# Sh2_MCU.net
KiCad netlist of a schematic drawn in Altium Designer
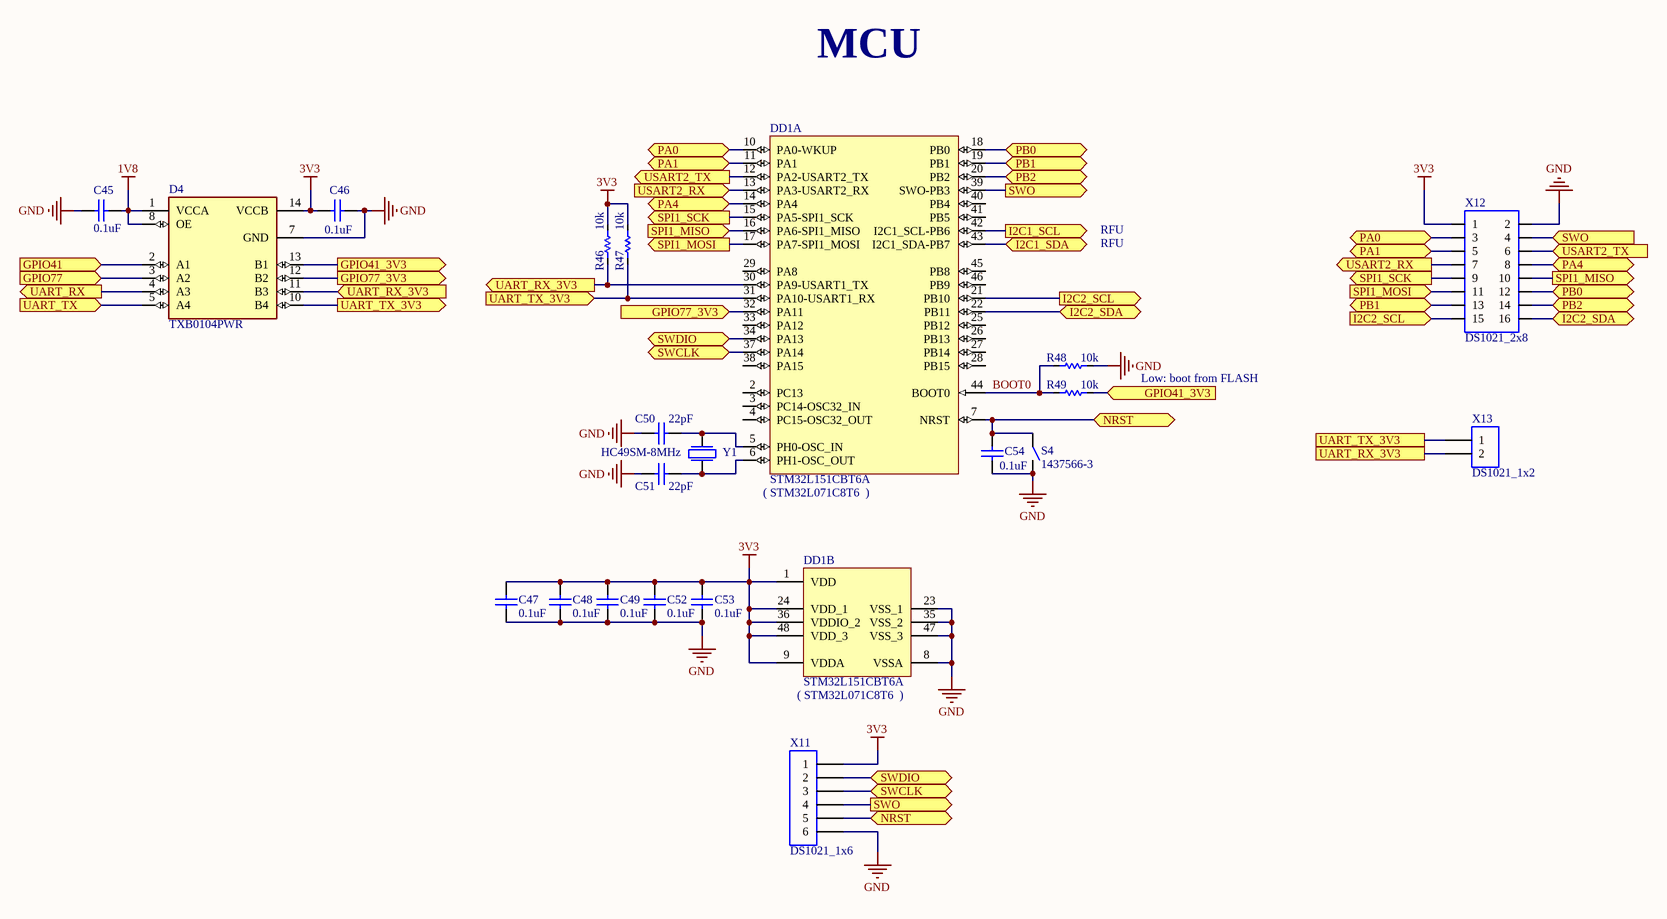
[diagram p0: Sh2_MCU.SchDoc]

(export (version "E")
  (design (tool "Eeschema 10.0.6"))
  (components
    (comp (ref "C45")
      (value "0.1uF")
      (footprint "C_SMD0603")
      (description "0603 SMD Capacitor")
      (libsource (lib "MyCompLib") (part "C_SMD"))
    )
    (comp (ref "C46")
      (value "0.1uF")
      (footprint "C_SMD0603")
      (description "0603 SMD Capacitor")
      (libsource (lib "MyCompLib") (part "C_SMD"))
    )
    (comp (ref "C47")
      (value "0.1uF")
      (footprint "C_SMD0603")
      (description "0603 SMD Capacitor")
      (libsource (lib "MyCompLib") (part "C_SMD"))
    )
    (comp (ref "C48")
      (value "0.1uF")
      (footprint "C_SMD0603")
      (description "0603 SMD Capacitor")
      (libsource (lib "MyCompLib") (part "C_SMD"))
    )
    (comp (ref "C49")
      (value "0.1uF")
      (footprint "C_SMD0603")
      (description "0603 SMD Capacitor")
      (libsource (lib "MyCompLib") (part "C_SMD"))
    )
    (comp (ref "C50")
      (value "22pF")
      (footprint "C_SMD0603")
      (description "0603 SMD Capacitor")
      (libsource (lib "MyCompLib") (part "C_SMD"))
    )
    (comp (ref "C51")
      (value "22pF")
      (footprint "C_SMD0603")
      (description "0603 SMD Capacitor")
      (libsource (lib "MyCompLib") (part "C_SMD"))
    )
    (comp (ref "C52")
      (value "0.1uF")
      (footprint "C_SMD0603")
      (description "0603 SMD Capacitor")
      (libsource (lib "MyCompLib") (part "C_SMD"))
    )
    (comp (ref "C53")
      (value "0.1uF")
      (footprint "C_SMD0603")
      (description "0603 SMD Capacitor")
      (libsource (lib "MyCompLib") (part "C_SMD"))
    )
    (comp (ref "C54")
      (value "0.1uF")
      (footprint "C_SMD0603")
      (description "0603 SMD Capacitor")
      (libsource (lib "MyCompLib") (part "C_SMD"))
    )
    (comp (ref "D4")
      (value "TXB0104PWR")
      (footprint "SOP65P640X120-14N")
      (fields (field (name "MF") "Texas Instruments"))
      (libsource (lib "MyCompLib") (part "TXB0104PWR"))
    )
    (comp (ref "DD1")
      (value "STM32L151CBT6A")
      (footprint "LQFP48_N")
      (fields (field (name "PARTNUMBER") "STM32F103C8T6"))
      (libsource (lib "MyCompLib") (part "STM32L151CBT6A"))
    )
    (comp (ref "R46")
      (value "10k")
      (footprint "R_SMD0603")
      (description "0603 SMD Resistor")
      (libsource (lib "MyCompLib") (part "R_SMD"))
    )
    (comp (ref "R47")
      (value "10k")
      (footprint "R_SMD0603")
      (description "0603 SMD Resistor")
      (libsource (lib "MyCompLib") (part "R_SMD"))
    )
    (comp (ref "R48")
      (value "10k")
      (footprint "R_SMD0603")
      (description "0603 SMD Resistor")
      (libsource (lib "MyCompLib") (part "R_SMD"))
    )
    (comp (ref "R49")
      (value "10k")
      (footprint "R_SMD0603")
      (description "0603 SMD Resistor")
      (libsource (lib "MyCompLib") (part "R_SMD"))
    )
    (comp (ref "S4")
      (value "1437566-3")
      (footprint "1437566-3")
      (description "SMD button")
      (libsource (lib "MyCompLib") (part "1437566-3"))
    )
    (comp (ref "X11")
      (value "DS1021_1x6")
      (footprint "PLD1X6")
      (description "Вилка штыревая 2.54мм 1x6 прямая тип1\r\n(PLS-6)")
      (libsource (lib "MyCompLib") (part "DS1021_1x6"))
    )
    (comp (ref "X12")
      (value "DS1021_2x8")
      (footprint "PLD2X8")
      (description "Вилка штыревая 2.54мм 2х8 прямая PLD-16")
      (libsource (lib "MyCompLib") (part "DS1021_2x8"))
    )
    (comp (ref "X13")
      (value "DS1021_1x2")
      (footprint "PLD2")
      (description "Вилка штыревая 2.54мм 1x2 прямая PLS-2")
      (libsource (lib "MyCompLib") (part "DS1021_1x2"))
    )
    (comp (ref "Y1")
      (value "HC49SM-8MHz")
      (footprint "HC49SM")
      (description "8 MHz resonator")
      (libsource (lib "MyCompLib") (part "HC49SM"))
    )
  )
  (nets
    (net (code "1") (name "/BOOT0") (class "Default")
      (node (ref "DD1") (pin "44") (pinfunction "BOOT0_44") (pintype "input"))
      (node (ref "R48") (pin "1") (pinfunction "CCW_1") (pintype "passive"))
      (node (ref "R49") (pin "1") (pinfunction "CCW_1") (pintype "passive"))
    )
    (net (code "2") (name "/GPIO41") (class "Default")
      (node (ref "D4") (pin "2") (pinfunction "A1_2") (pintype "bidirectional"))
    )
    (net (code "3") (name "/GPIO41_3V3") (class "Default")
      (node (ref "D4") (pin "13") (pinfunction "B1_13") (pintype "bidirectional"))
      (node (ref "R49") (pin "2") (pinfunction "CW_2") (pintype "passive"))
    )
    (net (code "4") (name "/GPIO77") (class "Default")
      (node (ref "D4") (pin "3") (pinfunction "A2_3") (pintype "bidirectional"))
    )
    (net (code "5") (name "/GPIO77_3V3") (class "Default")
      (node (ref "D4") (pin "12") (pinfunction "B2_12") (pintype "bidirectional"))
      (node (ref "DD1") (pin "32") (pinfunction "PA11_32") (pintype "bidirectional"))
    )
    (net (code "6") (name "/I2C1_SCL") (class "Default")
      (node (ref "DD1") (pin "42") (pinfunction "I2C1_SCL-PB6_42") (pintype "bidirectional"))
    )
    (net (code "7") (name "/I2C1_SDA") (class "Default")
      (node (ref "DD1") (pin "43") (pinfunction "I2C1_SDA-PB7_43") (pintype "bidirectional"))
    )
    (net (code "8") (name "/I2C2_SCL") (class "Default")
      (node (ref "DD1") (pin "21") (pinfunction "PB10_21") (pintype "bidirectional"))
      (node (ref "X12") (pin "15") (pinfunction "15_15") (pintype "passive"))
    )
    (net (code "9") (name "/I2C2_SDA") (class "Default")
      (node (ref "DD1") (pin "22") (pinfunction "PB11_22") (pintype "bidirectional"))
      (node (ref "X12") (pin "16") (pinfunction "16_16") (pintype "passive"))
    )
    (net (code "10") (name "/NRST") (class "Default")
      (node (ref "C54") (pin "1") (pinfunction "1_1") (pintype "passive"))
      (node (ref "DD1") (pin "7") (pinfunction "NRST_7") (pintype "bidirectional"))
      (node (ref "S4") (pin "1") (pinfunction "1_1") (pintype "passive"))
      (node (ref "X11") (pin "5") (pinfunction "5_5") (pintype "passive"))
    )
    (net (code "11") (name "/PA0") (class "Default")
      (node (ref "DD1") (pin "10") (pinfunction "PA0-WKUP_10") (pintype "bidirectional"))
      (node (ref "X12") (pin "3") (pinfunction "3_3") (pintype "passive"))
    )
    (net (code "12") (name "/PA1") (class "Default")
      (node (ref "DD1") (pin "11") (pinfunction "PA1_11") (pintype "bidirectional"))
      (node (ref "X12") (pin "5") (pinfunction "5_5") (pintype "passive"))
    )
    (net (code "13") (name "/PA4") (class "Default")
      (node (ref "DD1") (pin "14") (pinfunction "PA4_14") (pintype "bidirectional"))
      (node (ref "X12") (pin "8") (pinfunction "8_8") (pintype "passive"))
    )
    (net (code "14") (name "/PB0") (class "Default")
      (node (ref "DD1") (pin "18") (pinfunction "PB0_18") (pintype "bidirectional"))
      (node (ref "X12") (pin "12") (pinfunction "12_12") (pintype "passive"))
    )
    (net (code "15") (name "/PB1") (class "Default")
      (node (ref "DD1") (pin "19") (pinfunction "PB1_19") (pintype "bidirectional"))
      (node (ref "X12") (pin "13") (pinfunction "13_13") (pintype "passive"))
    )
    (net (code "16") (name "/PB2") (class "Default")
      (node (ref "DD1") (pin "20") (pinfunction "PB2_20") (pintype "bidirectional"))
      (node (ref "X12") (pin "14") (pinfunction "14_14") (pintype "passive"))
    )
    (net (code "17") (name "/SPI1_MISO") (class "Default")
      (node (ref "DD1") (pin "16") (pinfunction "PA6-SPI1_MISO_16") (pintype "bidirectional"))
      (node (ref "X12") (pin "10") (pinfunction "10_10") (pintype "passive"))
    )
    (net (code "18") (name "/SPI1_MOSI") (class "Default")
      (node (ref "DD1") (pin "17") (pinfunction "PA7-SPI1_MOSI_17") (pintype "bidirectional"))
      (node (ref "X12") (pin "11") (pinfunction "11_11") (pintype "passive"))
    )
    (net (code "19") (name "/SPI1_SCK") (class "Default")
      (node (ref "DD1") (pin "15") (pinfunction "PA5-SPI1_SCK_15") (pintype "bidirectional"))
      (node (ref "X12") (pin "9") (pinfunction "9_9") (pintype "passive"))
    )
    (net (code "20") (name "/SWCLK") (class "Default")
      (node (ref "DD1") (pin "37") (pinfunction "PA14_37") (pintype "bidirectional"))
      (node (ref "X11") (pin "3") (pinfunction "3_3") (pintype "passive"))
    )
    (net (code "21") (name "/SWDIO") (class "Default")
      (node (ref "DD1") (pin "34") (pinfunction "PA13_34") (pintype "bidirectional"))
      (node (ref "X11") (pin "2") (pinfunction "2_2") (pintype "passive"))
    )
    (net (code "22") (name "/SWO") (class "Default")
      (node (ref "DD1") (pin "39") (pinfunction "SWO-PB3_39") (pintype "bidirectional"))
      (node (ref "X11") (pin "4") (pinfunction "4_4") (pintype "passive"))
      (node (ref "X12") (pin "4") (pinfunction "4_4") (pintype "passive"))
    )
    (net (code "23") (name "/UART_RX") (class "Default")
      (node (ref "D4") (pin "4") (pinfunction "A3_4") (pintype "bidirectional"))
    )
    (net (code "24") (name "/UART_RX_3V3") (class "Default")
      (node (ref "D4") (pin "11") (pinfunction "B3_11") (pintype "bidirectional"))
      (node (ref "DD1") (pin "30") (pinfunction "PA9-USART1_TX_30") (pintype "bidirectional"))
      (node (ref "R46") (pin "2") (pinfunction "CW_2") (pintype "passive"))
      (node (ref "X13") (pin "2") (pinfunction "2_2") (pintype "passive"))
    )
    (net (code "25") (name "/UART_TX") (class "Default")
      (node (ref "D4") (pin "5") (pinfunction "A4_5") (pintype "bidirectional"))
    )
    (net (code "26") (name "/UART_TX_3V3") (class "Default")
      (node (ref "D4") (pin "10") (pinfunction "B4_10") (pintype "bidirectional"))
      (node (ref "DD1") (pin "31") (pinfunction "PA10-USART1_RX_31") (pintype "bidirectional"))
      (node (ref "R47") (pin "2") (pinfunction "CW_2") (pintype "passive"))
      (node (ref "X13") (pin "1") (pinfunction "1_1") (pintype "passive"))
    )
    (net (code "27") (name "/USART2_RX") (class "Default")
      (node (ref "DD1") (pin "13") (pinfunction "PA3-USART2_RX_13") (pintype "bidirectional"))
      (node (ref "X12") (pin "7") (pinfunction "7_7") (pintype "passive"))
    )
    (net (code "28") (name "/USART2_TX") (class "Default")
      (node (ref "DD1") (pin "12") (pinfunction "PA2-USART2_TX_12") (pintype "bidirectional"))
      (node (ref "X12") (pin "6") (pinfunction "6_6") (pintype "passive"))
    )
    (net (code "29") (name "1V8") (class "Default")
      (node (ref "C45") (pin "1") (pinfunction "1_1") (pintype "passive"))
      (node (ref "D4") (pin "1") (pinfunction "VCCA_1") (pintype "power_in"))
      (node (ref "D4") (pin "8") (pinfunction "OE_8") (pintype "bidirectional"))
    )
    (net (code "30") (name "3V3") (class "Default")
      (node (ref "C46") (pin "2") (pinfunction "2_2") (pintype "passive"))
      (node (ref "C47") (pin "1") (pinfunction "1_1") (pintype "passive"))
      (node (ref "C48") (pin "1") (pinfunction "1_1") (pintype "passive"))
      (node (ref "C49") (pin "1") (pinfunction "1_1") (pintype "passive"))
      (node (ref "C52") (pin "1") (pinfunction "1_1") (pintype "passive"))
      (node (ref "C53") (pin "1") (pinfunction "1_1") (pintype "passive"))
      (node (ref "D4") (pin "14") (pinfunction "VCCB_14") (pintype "power_in"))
      (node (ref "DD1") (pin "1") (pinfunction "VDD_1") (pintype "power_in"))
      (node (ref "DD1") (pin "24") (pinfunction "VDD_1_24") (pintype "power_in"))
      (node (ref "DD1") (pin "36") (pinfunction "VDDIO_2_36") (pintype "power_in"))
      (node (ref "DD1") (pin "48") (pinfunction "VDD_3_48") (pintype "power_in"))
      (node (ref "DD1") (pin "9") (pinfunction "VDDA_9") (pintype "power_in"))
      (node (ref "R46") (pin "1") (pinfunction "CCW_1") (pintype "passive"))
      (node (ref "R47") (pin "1") (pinfunction "CCW_1") (pintype "passive"))
      (node (ref "X11") (pin "1") (pinfunction "1_1") (pintype "passive"))
      (node (ref "X12") (pin "1") (pinfunction "1_1") (pintype "passive"))
    )
    (net (code "31") (name "GND") (class "Default")
      (node (ref "C45") (pin "2") (pinfunction "2_2") (pintype "passive"))
      (node (ref "C46") (pin "1") (pinfunction "1_1") (pintype "passive"))
      (node (ref "C47") (pin "2") (pinfunction "2_2") (pintype "passive"))
      (node (ref "C48") (pin "2") (pinfunction "2_2") (pintype "passive"))
      (node (ref "C49") (pin "2") (pinfunction "2_2") (pintype "passive"))
      (node (ref "C50") (pin "1") (pinfunction "1_1") (pintype "passive"))
      (node (ref "C51") (pin "1") (pinfunction "1_1") (pintype "passive"))
      (node (ref "C52") (pin "2") (pinfunction "2_2") (pintype "passive"))
      (node (ref "C53") (pin "2") (pinfunction "2_2") (pintype "passive"))
      (node (ref "C54") (pin "2") (pinfunction "2_2") (pintype "passive"))
      (node (ref "D4") (pin "7") (pinfunction "GND_7") (pintype "power_in"))
      (node (ref "DD1") (pin "23") (pinfunction "VSS_1_23") (pintype "power_in"))
      (node (ref "DD1") (pin "35") (pinfunction "VSS_2_35") (pintype "power_in"))
      (node (ref "DD1") (pin "47") (pinfunction "VSS_3_47") (pintype "power_in"))
      (node (ref "DD1") (pin "8") (pinfunction "VSSA_8") (pintype "power_in"))
      (node (ref "R48") (pin "2") (pinfunction "CW_2") (pintype "passive"))
      (node (ref "S4") (pin "2") (pinfunction "2_2") (pintype "passive"))
      (node (ref "X11") (pin "6") (pinfunction "6_6") (pintype "passive"))
      (node (ref "X12") (pin "2") (pinfunction "2_2") (pintype "passive"))
    )
    (net (code "32") (name "Net-(DD1A-PH0-OSC_IN)") (class "Default")
      (node (ref "C50") (pin "2") (pinfunction "2_2") (pintype "passive"))
      (node (ref "DD1") (pin "5") (pinfunction "PH0-OSC_IN_5") (pintype "bidirectional"))
      (node (ref "Y1") (pin "2") (pinfunction "2_2") (pintype "passive"))
    )
    (net (code "33") (name "Net-(DD1A-PH1-OSC_OUT)") (class "Default")
      (node (ref "C51") (pin "2") (pinfunction "2_2") (pintype "passive"))
      (node (ref "DD1") (pin "6") (pinfunction "PH1-OSC_OUT_6") (pintype "bidirectional"))
      (node (ref "Y1") (pin "1") (pinfunction "1_1") (pintype "passive"))
    )
    (net (code "34") (name "unconnected-(DD1A-PA8-Pad29)") (class "Default")
      (node (ref "DD1") (pin "29") (pinfunction "PA8_29") (pintype "bidirectional"))
    )
    (net (code "35") (name "unconnected-(DD1A-PA12-Pad33)") (class "Default")
      (node (ref "DD1") (pin "33") (pinfunction "PA12_33") (pintype "bidirectional"))
    )
    (net (code "36") (name "unconnected-(DD1A-PA15-Pad38)") (class "Default")
      (node (ref "DD1") (pin "38") (pinfunction "PA15_38") (pintype "bidirectional"))
    )
    (net (code "37") (name "unconnected-(DD1A-PB4-Pad40)") (class "Default")
      (node (ref "DD1") (pin "40") (pinfunction "PB4_40") (pintype "bidirectional"))
    )
    (net (code "38") (name "unconnected-(DD1A-PB5-Pad41)") (class "Default")
      (node (ref "DD1") (pin "41") (pinfunction "PB5_41") (pintype "bidirectional"))
    )
    (net (code "39") (name "unconnected-(DD1A-PB8-Pad45)") (class "Default")
      (node (ref "DD1") (pin "45") (pinfunction "PB8_45") (pintype "bidirectional"))
    )
    (net (code "40") (name "unconnected-(DD1A-PB9-Pad46)") (class "Default")
      (node (ref "DD1") (pin "46") (pinfunction "PB9_46") (pintype "bidirectional"))
    )
    (net (code "41") (name "unconnected-(DD1A-PB12-Pad25)") (class "Default")
      (node (ref "DD1") (pin "25") (pinfunction "PB12_25") (pintype "bidirectional"))
    )
    (net (code "42") (name "unconnected-(DD1A-PB13-Pad26)") (class "Default")
      (node (ref "DD1") (pin "26") (pinfunction "PB13_26") (pintype "bidirectional"))
    )
    (net (code "43") (name "unconnected-(DD1A-PB14-Pad27)") (class "Default")
      (node (ref "DD1") (pin "27") (pinfunction "PB14_27") (pintype "bidirectional"))
    )
    (net (code "44") (name "unconnected-(DD1A-PB15-Pad28)") (class "Default")
      (node (ref "DD1") (pin "28") (pinfunction "PB15_28") (pintype "bidirectional"))
    )
    (net (code "45") (name "unconnected-(DD1A-PC13-Pad2)") (class "Default")
      (node (ref "DD1") (pin "2") (pinfunction "PC13_2") (pintype "bidirectional"))
    )
    (net (code "46") (name "unconnected-(DD1A-PC14-OSC32_IN-Pad3)") (class "Default")
      (node (ref "DD1") (pin "3") (pinfunction "PC14-OSC32_IN_3") (pintype "bidirectional"))
    )
    (net (code "47") (name "unconnected-(DD1A-PC15-OSC32_OUT-Pad4)") (class "Default")
      (node (ref "DD1") (pin "4") (pinfunction "PC15-OSC32_OUT_4") (pintype "bidirectional"))
    )
  )
)
